# MCU.net
KiCad netlist of a schematic drawn in Altium Designer
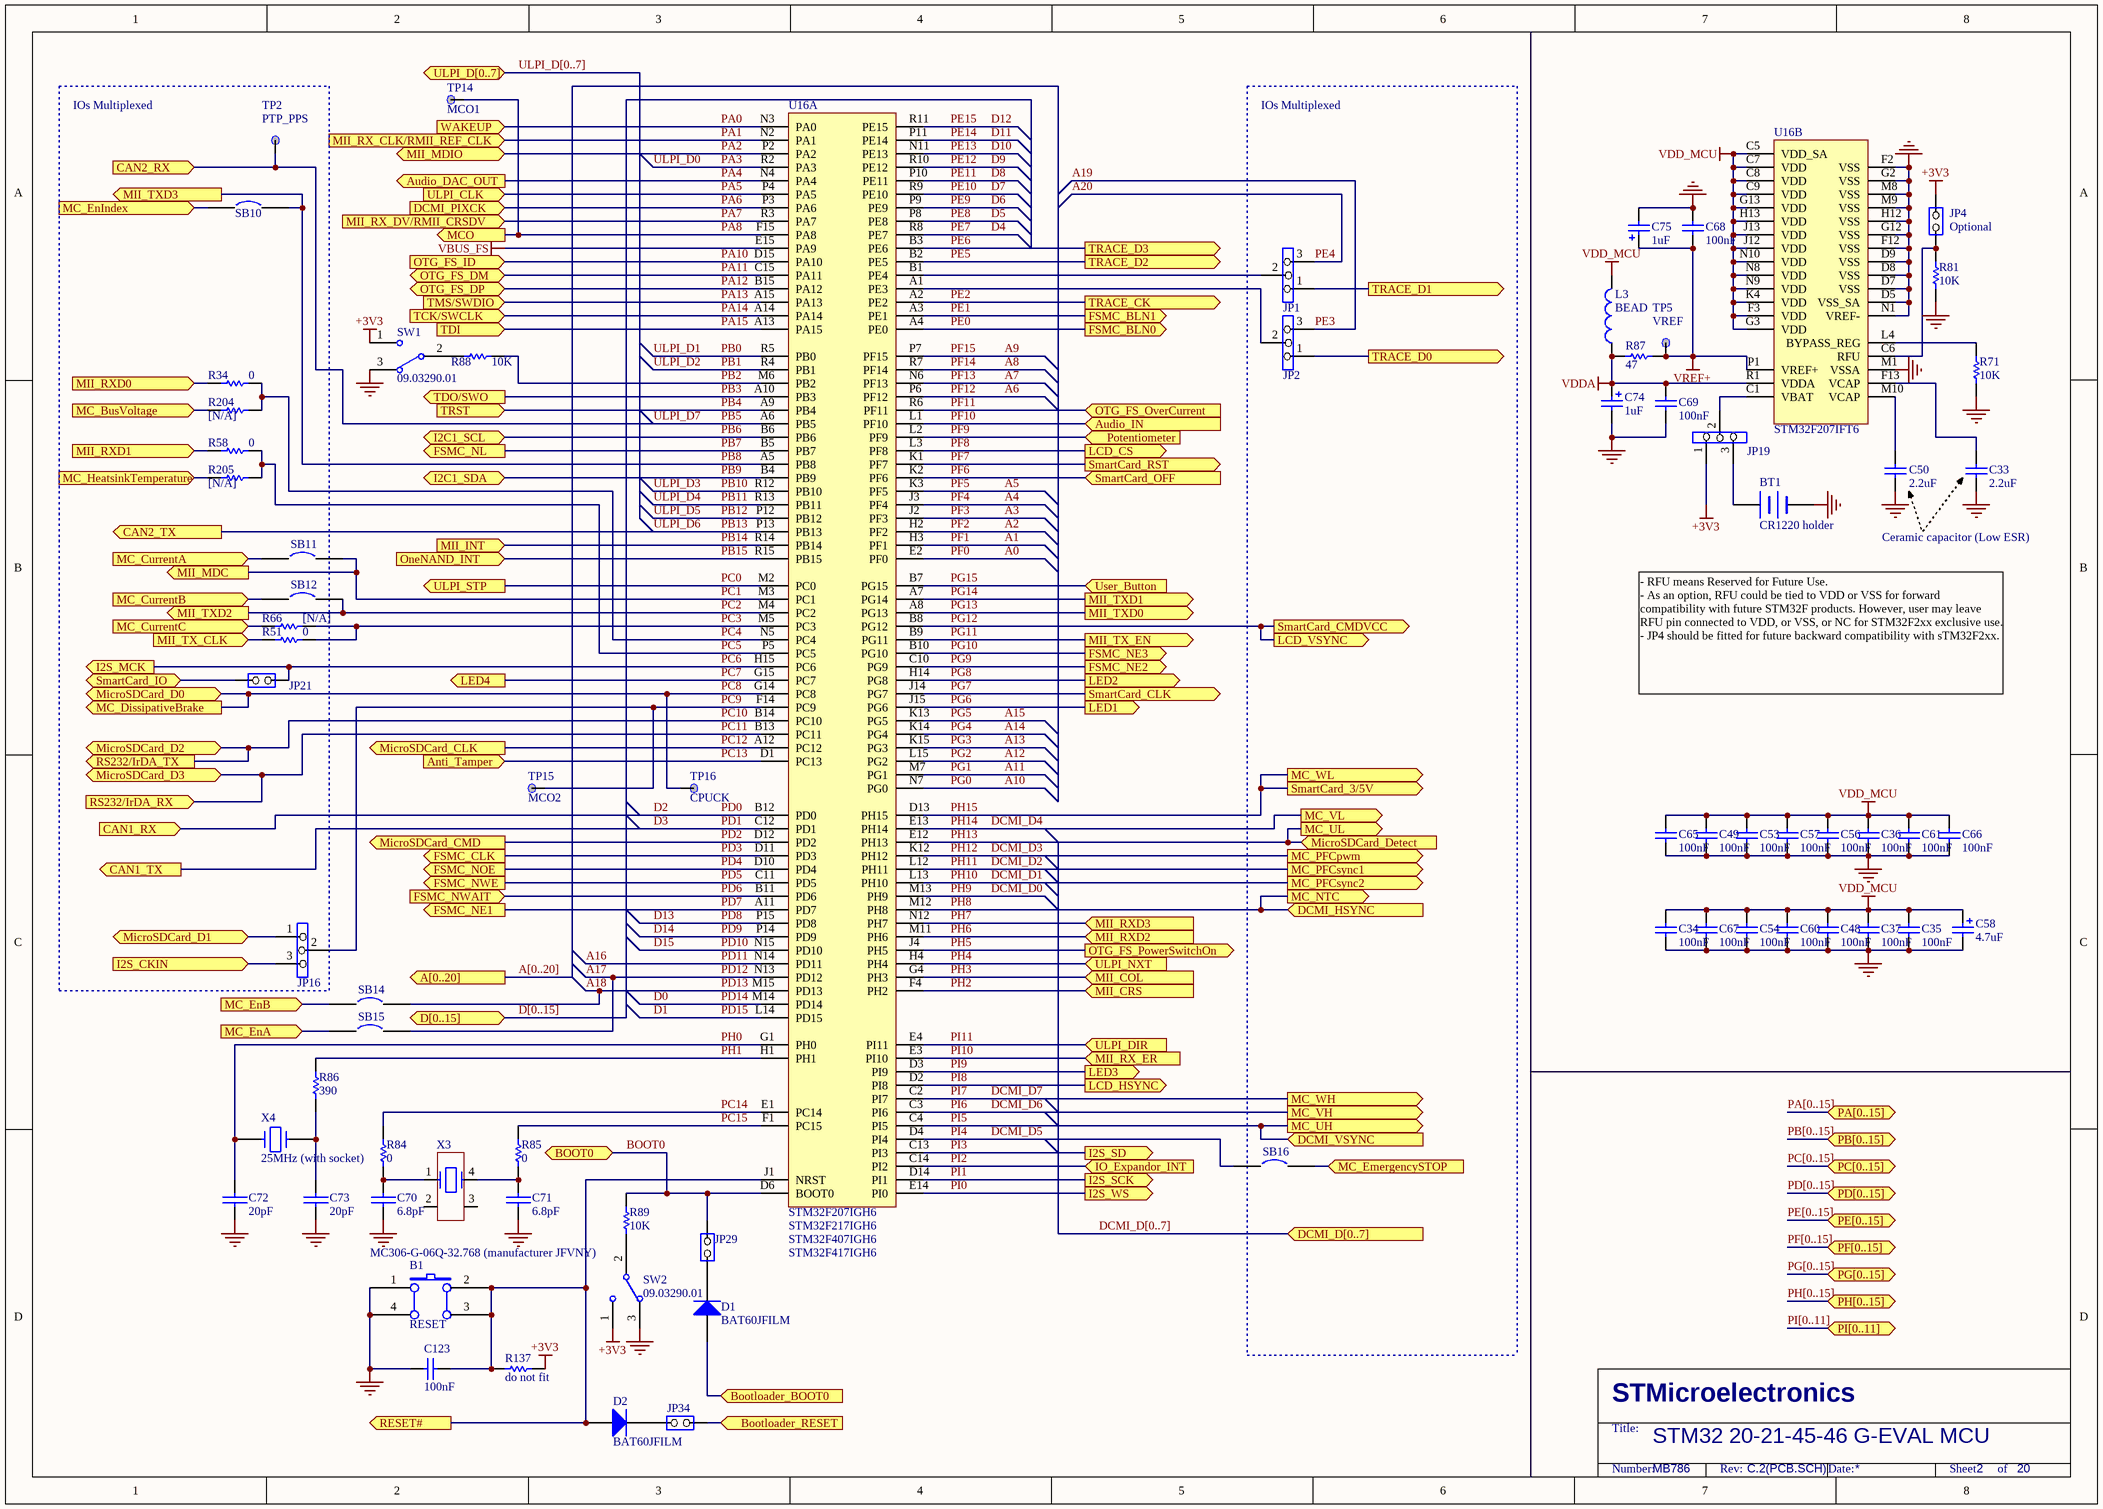
[diagram p0: MCU.SchDoc]

(export (version "E")
  (design (tool "Eeschema 10.0.6"))
  (components
    (comp (ref "B1")
      (value "RESET")
      (footprint "PB10")
      (description "SE PUSHBUTTON")
      (libsource (lib "Documents") (part "SW PUSHBUTTON"))
    )
    (comp (ref "BT1")
      (value "CR1220 holder")
      (footprint "LI1220_1")
      (description "Battery")
      (libsource (lib "*") (part "BATTERY"))
    )
    (comp (ref "C33")
      (value "2.2uF")
      (footprint "1206C")
      (description "Capacitor")
      (fields (field (name "PUBLISHER") "Altium Limited"))
      (libsource (lib "Miscellaneous Devices") (part "Cap"))
    )
    (comp (ref "C34")
      (value "100nF")
      (footprint "0402C")
      (description "Capacitor")
      (fields (field (name "PUBLISHER") "Altium Limited"))
      (libsource (lib "Miscellaneous Devices") (part "Cap"))
    )
    (comp (ref "C35")
      (value "100nF")
      (footprint "0402C")
      (description "Capacitor")
      (fields (field (name "PUBLISHER") "Altium Limited"))
      (libsource (lib "Miscellaneous Devices") (part "Cap"))
    )
    (comp (ref "C36")
      (value "100nF")
      (footprint "0402C")
      (description "Capacitor")
      (fields (field (name "PUBLISHER") "Altium Limited"))
      (libsource (lib "Miscellaneous Devices") (part "Cap"))
    )
    (comp (ref "C37")
      (value "100nF")
      (footprint "0402C")
      (description "Capacitor")
      (fields (field (name "PUBLISHER") "Altium Limited"))
      (libsource (lib "Miscellaneous Devices") (part "Cap"))
    )
    (comp (ref "C48")
      (value "100nF")
      (footprint "0402C")
      (description "Capacitor")
      (fields (field (name "PUBLISHER") "Altium Limited"))
      (libsource (lib "Miscellaneous Devices") (part "Cap"))
    )
    (comp (ref "C49")
      (value "100nF")
      (footprint "0402C")
      (description "Capacitor")
      (fields (field (name "PUBLISHER") "Altium Limited"))
      (libsource (lib "Miscellaneous Devices") (part "Cap"))
    )
    (comp (ref "C50")
      (value "2.2uF")
      (footprint "1206C")
      (description "Capacitor")
      (fields (field (name "PUBLISHER") "Altium Limited"))
      (libsource (lib "Miscellaneous Devices") (part "Cap"))
    )
    (comp (ref "C53")
      (value "100nF")
      (footprint "0402C")
      (description "Capacitor")
      (fields (field (name "PUBLISHER") "Altium Limited"))
      (libsource (lib "Miscellaneous Devices") (part "Cap"))
    )
    (comp (ref "C54")
      (value "100nF")
      (footprint "0402C")
      (description "Capacitor")
      (fields (field (name "PUBLISHER") "Altium Limited"))
      (libsource (lib "Miscellaneous Devices") (part "Cap"))
    )
    (comp (ref "C56")
      (value "100nF")
      (footprint "0402C")
      (description "Capacitor")
      (fields (field (name "PUBLISHER") "Altium Limited"))
      (libsource (lib "Miscellaneous Devices") (part "Cap"))
    )
    (comp (ref "C57")
      (value "100nF")
      (footprint "0402C")
      (description "Capacitor")
      (fields (field (name "PUBLISHER") "Altium Limited"))
      (libsource (lib "Miscellaneous Devices") (part "Cap"))
    )
    (comp (ref "C58")
      (value "4.7uF")
      (footprint "TAN-A")
      (description "Polarized Capacitor (Radial)")
      (fields (field (name "PUBLISHER") "Altium Limited"))
      (libsource (lib "Miscellaneous Devices") (part "Cap Pol1"))
    )
    (comp (ref "C60")
      (value "100nF")
      (footprint "0402C")
      (description "Capacitor")
      (fields (field (name "PUBLISHER") "Altium Limited"))
      (libsource (lib "Miscellaneous Devices") (part "Cap"))
    )
    (comp (ref "C61")
      (value "100nF")
      (footprint "0402C")
      (description "Capacitor")
      (fields (field (name "PUBLISHER") "Altium Limited"))
      (libsource (lib "Miscellaneous Devices") (part "Cap"))
    )
    (comp (ref "C65")
      (value "100nF")
      (footprint "0402C")
      (description "Capacitor")
      (fields (field (name "PUBLISHER") "Altium Limited"))
      (libsource (lib "Miscellaneous Devices") (part "Cap"))
    )
    (comp (ref "C66")
      (value "100nF")
      (footprint "0402C")
      (description "Capacitor")
      (fields (field (name "PUBLISHER") "Altium Limited"))
      (libsource (lib "Miscellaneous Devices") (part "Cap"))
    )
    (comp (ref "C67")
      (value "100nF")
      (footprint "0402C")
      (description "Capacitor")
      (fields (field (name "PUBLISHER") "Altium Limited"))
      (libsource (lib "Miscellaneous Devices") (part "Cap"))
    )
    (comp (ref "C68")
      (value "100nF")
      (footprint "0402C")
      (description "Capacitor")
      (fields (field (name "PUBLISHER") "Altium Limited"))
      (libsource (lib "Miscellaneous Devices") (part "Cap"))
    )
    (comp (ref "C69")
      (value "100nF")
      (footprint "0402C")
      (description "Capacitor")
      (fields (field (name "PUBLISHER") "Altium Limited"))
      (libsource (lib "Miscellaneous Devices") (part "Cap"))
    )
    (comp (ref "C70")
      (value "6.8pF")
      (footprint "0603C")
      (description "Capacitor")
      (libsource (lib "*") (part "CAP"))
    )
    (comp (ref "C71")
      (value "6.8pF")
      (footprint "0603C")
      (description "Capacitor")
      (libsource (lib "*") (part "CAP"))
    )
    (comp (ref "C72")
      (value "20pF")
      (footprint "0603C")
      (description "Capacitor")
      (libsource (lib "") (part "CAP_1"))
    )
    (comp (ref "C73")
      (value "20pF")
      (footprint "0603C")
      (description "Capacitor")
      (libsource (lib "") (part "CAP_1"))
    )
    (comp (ref "C74")
      (value "1uF")
      (footprint "TAN-A")
      (description "Polarized Capacitor (Radial)")
      (fields (field (name "PUBLISHER") "Altium Limited"))
      (libsource (lib "Miscellaneous Devices") (part "Cap Pol1"))
    )
    (comp (ref "C75")
      (value "1uF")
      (footprint "TAN-A")
      (description "Polarized Capacitor (Radial)")
      (fields (field (name "PUBLISHER") "Altium Limited"))
      (libsource (lib "Miscellaneous Devices") (part "Cap Pol1"))
    )
    (comp (ref "C123")
      (value "100nF")
      (footprint "0402C")
      (description "Capacitor")
      (fields (field (name "PUBLISHER") "Altium Limited"))
      (libsource (lib "Miscellaneous Devices") (part "CAP"))
    )
    (comp (ref "D1")
      (value "BAT60JFILM")
      (footprint "SOD-323")
      (description "Default Diode")
      (fields (field (name "PUBLISHER") "Altium Limited"))
      (libsource (lib "Miscellaneous Devices") (part "Diode"))
    )
    (comp (ref "D2")
      (value "BAT60JFILM")
      (footprint "SOD-323")
      (description "Default Diode")
      (fields (field (name "PUBLISHER") "Altium Limited"))
      (libsource (lib "Miscellaneous Devices") (part "Diode"))
    )
    (comp (ref "JP1") (value "~") (footprint "SIP3") (libsource (lib "STR910_SCHLIB") (part "Jumper3")))
    (comp (ref "JP2") (value "~") (footprint "SIP3") (libsource (lib "STR910_SCHLIB") (part "Jumper3")))
    (comp (ref "JP4") (value "~") (footprint "SIP2") (libsource (lib "*") (part "JP2")))
    (comp (ref "JP16") (value "~") (footprint "SIP3") (libsource (lib "STR910_SCHLIB") (part "Jumper3")))
    (comp (ref "JP19") (value "~") (footprint "SIP3") (libsource (lib "STR910_SCHLIB") (part "Jumper3")))
    (comp (ref "JP21") (value "~") (footprint "SIP2") (libsource (lib "*") (part "JP2")))
    (comp (ref "JP29") (value "~") (footprint "SIP2") (libsource (lib "*") (part "JP2")))
    (comp (ref "JP34") (value "~") (footprint "SIP2") (libsource (lib "*") (part "JP2")))
    (comp (ref "L3")
      (value "BEAD")
      (footprint "0603L")
      (description "Inductor")
      (fields (field (name "PUBLISHER") "Altium Limited"))
      (libsource (lib "Miscellaneous Devices") (part "Inductor"))
    )
    (comp (ref "R34")
      (value "0")
      (footprint "0603R")
      (description "Resistor")
      (fields (field (name "PUBLISHER") "Altium Limited"))
      (libsource (lib "Miscellaneous Devices") (part "res1"))
    )
    (comp (ref "R51")
      (value "0")
      (footprint "0603R")
      (description "Resistor")
      (fields (field (name "PUBLISHER") "Altium Limited"))
      (libsource (lib "Miscellaneous Devices") (part "res1"))
    )
    (comp (ref "R58")
      (value "0")
      (footprint "0603R")
      (description "Resistor")
      (fields (field (name "PUBLISHER") "Altium Limited"))
      (libsource (lib "Miscellaneous Devices") (part "res1"))
    )
    (comp (ref "R66")
      (value "[N/A]")
      (footprint "0603R")
      (description "Resistor")
      (fields (field (name "PUBLISHER") "Altium Limited"))
      (libsource (lib "Miscellaneous Devices") (part "res1"))
    )
    (comp (ref "R71")
      (value "10K")
      (footprint "0402R")
      (description "Resistor")
      (fields (field (name "PUBLISHER") "Altium Limited"))
      (libsource (lib "Miscellaneous Devices") (part "Res1"))
    )
    (comp (ref "R81")
      (value "10K")
      (footprint "0402R")
      (description "Resistor")
      (fields (field (name "PUBLISHER") "Altium Limited"))
      (libsource (lib "Miscellaneous Devices") (part "Res1"))
    )
    (comp (ref "R84")
      (value "0")
      (footprint "0603R")
      (description "Resistor")
      (fields (field (name "PUBLISHER") "Altium Limited"))
      (libsource (lib "Miscellaneous Devices") (part "Res1"))
    )
    (comp (ref "R85")
      (value "0")
      (footprint "0603R")
      (description "Resistor")
      (fields (field (name "PUBLISHER") "Altium Limited"))
      (libsource (lib "Miscellaneous Devices") (part "Res1"))
    )
    (comp (ref "R86")
      (value "390")
      (footprint "0603R")
      (description "Resistor")
      (fields (field (name "PUBLISHER") "Altium Limited"))
      (libsource (lib "Miscellaneous Devices") (part "Res1"))
    )
    (comp (ref "R87")
      (value "47")
      (footprint "0603R")
      (description "Resistor")
      (fields (field (name "PUBLISHER") "Altium Limited"))
      (libsource (lib "Miscellaneous Devices") (part "Res1"))
    )
    (comp (ref "R88")
      (value "10K")
      (footprint "0402R")
      (description "Resistor")
      (fields (field (name "PUBLISHER") "Altium Limited"))
      (libsource (lib "Miscellaneous Devices") (part "res1"))
    )
    (comp (ref "R89")
      (value "10K")
      (footprint "0402R")
      (description "Resistor")
      (fields (field (name "PUBLISHER") "Altium Limited"))
      (libsource (lib "Miscellaneous Devices") (part "res1"))
    )
    (comp (ref "R137")
      (value "do not fit")
      (footprint "0603R")
      (description "Resistor")
      (fields (field (name "PUBLISHER") "Altium Limited"))
      (libsource (lib "Miscellaneous Devices") (part "res1"))
    )
    (comp (ref "R204")
      (value "[N/A]")
      (footprint "0603R")
      (description "Resistor")
      (fields (field (name "PUBLISHER") "Altium Limited"))
      (libsource (lib "Miscellaneous Devices") (part "res1"))
    )
    (comp (ref "R205")
      (value "[N/A]")
      (footprint "0603R")
      (description "Resistor")
      (fields (field (name "PUBLISHER") "Altium Limited"))
      (libsource (lib "Miscellaneous Devices") (part "res1"))
    )
    (comp (ref "SB10")
      (value "~")
      (footprint "JP2_SMD")
      (description "Circuit Breaker")
      (fields (field (name "PUBLISHER") "Altium Limited"))
      (libsource (lib "Miscellaneous Devices") (part "Circuit Breaker"))
    )
    (comp (ref "SB11")
      (value "~")
      (footprint "JP2_SMD")
      (description "Circuit Breaker")
      (fields (field (name "PUBLISHER") "Altium Limited"))
      (libsource (lib "Miscellaneous Devices") (part "Circuit Breaker"))
    )
    (comp (ref "SB12")
      (value "~")
      (footprint "JP2_SMD")
      (description "Circuit Breaker")
      (fields (field (name "PUBLISHER") "Altium Limited"))
      (libsource (lib "Miscellaneous Devices") (part "Circuit Breaker"))
    )
    (comp (ref "SB14")
      (value "~")
      (footprint "JP2_SMD")
      (description "Circuit Breaker")
      (fields (field (name "PUBLISHER") "Altium Limited"))
      (libsource (lib "Miscellaneous Devices") (part "Circuit Breaker"))
    )
    (comp (ref "SB15")
      (value "~")
      (footprint "JP2_SMD")
      (description "Circuit Breaker")
      (fields (field (name "PUBLISHER") "Altium Limited"))
      (libsource (lib "Miscellaneous Devices") (part "Circuit Breaker"))
    )
    (comp (ref "SB16")
      (value "~")
      (footprint "JP2_SMD")
      (description "Circuit Breaker")
      (fields (field (name "PUBLISHER") "Altium Limited"))
      (libsource (lib "Miscellaneous Devices") (part "Circuit Breaker"))
    )
    (comp (ref "SW1")
      (value "09.03290.01")
      (footprint "SIP3")
      (description "SPDT Subminiature Toggle Switch, Right Angle Mounting, Vertical Actuation")
      (fields (field (name "PUBLISHER") "Altium Limited"))
      (libsource (lib "Miscellaneous Devices") (part "SW-SPDT"))
    )
    (comp (ref "SW2")
      (value "09.03290.01")
      (footprint "SIP3")
      (description "SPDT Subminiature Toggle Switch, Right Angle Mounting, Vertical Actuation")
      (fields (field (name "PUBLISHER") "Altium Limited"))
      (libsource (lib "Miscellaneous Devices") (part "SW-SPDT"))
    )
    (comp (ref "TP2") (value "PTP_PPS") (footprint "TP") (libsource (lib "*") (part "TP")))
    (comp (ref "TP5") (value "VREF") (footprint "TP") (libsource (lib "*") (part "TP")))
    (comp (ref "TP14") (value "MCO1") (footprint "TP") (libsource (lib "*") (part "TP")))
    (comp (ref "TP15") (value "MCO2") (footprint "TP") (libsource (lib "*") (part "TP")))
    (comp (ref "TP16") (value "CPUCK") (footprint "TP") (libsource (lib "*") (part "TP")))
    (comp (ref "U16")
      (value "STM32F207IGH6")
      (footprint "UFBGA176")
      (libsource (lib "") (part "MANGUSTA_BGA176_1"))
    )
    (comp (ref "X3")
      (value "MC306-G-06Q-32.768 (manufacturer JFVNY)")
      (footprint "SM8")
      (libsource (lib "*") (part "MC306"))
    )
    (comp (ref "X4")
      (value "25MHz (with socket)")
      (footprint "XTAL_socket")
      (description "Crystal")
      (libsource (lib "*") (part "CRYSTAL"))
    )
  )
  (nets
    (net (code "2") (name "+3V3") (class "Default")
      (node (ref "JP19") (pin "1") (pintype "passive"))
      (node (ref "JP4") (pin "1") (pinfunction "COMMON_1") (pintype "passive"))
      (node (ref "R137") (pin "2") (pinfunction "2_2") (pintype "passive"))
      (node (ref "SW1") (pin "1") (pintype "passive"))
      (node (ref "SW2") (pin "1") (pintype "passive"))
    )
    (net (code "3") (name "/A0") (class "Default")
      (node (ref "U16") (pin "E2") (pinfunction "PF0_E2") (pintype "passive"))
    )
    (net (code "4") (name "/A1") (class "Default")
      (node (ref "U16") (pin "H3") (pinfunction "PF1_H3") (pintype "passive"))
    )
    (net (code "5") (name "/A2") (class "Default")
      (node (ref "U16") (pin "H2") (pinfunction "PF2_H2") (pintype "passive"))
    )
    (net (code "6") (name "/A3") (class "Default")
      (node (ref "U16") (pin "J2") (pinfunction "PF3_J2") (pintype "passive"))
    )
    (net (code "7") (name "/A4") (class "Default")
      (node (ref "U16") (pin "J3") (pinfunction "PF4_J3") (pintype "passive"))
    )
    (net (code "8") (name "/A5") (class "Default")
      (node (ref "U16") (pin "K3") (pinfunction "PF5_K3") (pintype "passive"))
    )
    (net (code "9") (name "/A6") (class "Default")
      (node (ref "U16") (pin "P6") (pinfunction "PF12_P6") (pintype "passive"))
    )
    (net (code "10") (name "/A7") (class "Default")
      (node (ref "U16") (pin "N6") (pinfunction "PF13_N6") (pintype "passive"))
    )
    (net (code "11") (name "/A8") (class "Default")
      (node (ref "U16") (pin "R7") (pinfunction "PF14_R7") (pintype "passive"))
    )
    (net (code "12") (name "/A9") (class "Default")
      (node (ref "U16") (pin "P7") (pinfunction "PF15_P7") (pintype "passive"))
    )
    (net (code "13") (name "/A10") (class "Default")
      (node (ref "U16") (pin "N7") (pinfunction "PG0_N7") (pintype "passive"))
    )
    (net (code "14") (name "/A11") (class "Default")
      (node (ref "U16") (pin "M7") (pinfunction "PG1_M7") (pintype "passive"))
    )
    (net (code "15") (name "/A12") (class "Default")
      (node (ref "U16") (pin "L15") (pinfunction "PG2_L15") (pintype "passive"))
    )
    (net (code "16") (name "/A13") (class "Default")
      (node (ref "U16") (pin "K15") (pinfunction "PG3_K15") (pintype "passive"))
    )
    (net (code "17") (name "/A14") (class "Default")
      (node (ref "U16") (pin "K14") (pinfunction "PG4_K14") (pintype "passive"))
    )
    (net (code "18") (name "/A15") (class "Default")
      (node (ref "U16") (pin "K13") (pinfunction "PG5_K13") (pintype "passive"))
    )
    (net (code "19") (name "/A16") (class "Default")
      (node (ref "U16") (pin "N14") (pinfunction "PD11_N14") (pintype "passive"))
    )
    (net (code "20") (name "/A17") (class "Default")
      (node (ref "SB15") (pin "2") (pinfunction "2_2") (pintype "passive"))
      (node (ref "U16") (pin "N13") (pinfunction "PD12_N13") (pintype "passive"))
    )
    (net (code "21") (name "/A18") (class "Default")
      (node (ref "SB14") (pin "2") (pinfunction "2_2") (pintype "passive"))
      (node (ref "U16") (pin "M15") (pinfunction "PD13_M15") (pintype "passive"))
    )
    (net (code "22") (name "/A19") (class "Default") (node (ref "JP2") (pin "3") (pintype "passive")))
    (net (code "23") (name "/A20") (class "Default") (node (ref "JP1") (pin "3") (pintype "passive")))
    (net (code "25") (name "/BOOT0") (class "Default")
      (node (ref "JP29") (pin "1") (pinfunction "COMMON_1") (pintype "passive"))
      (node (ref "R89") (pin "1") (pinfunction "1_1") (pintype "passive"))
      (node (ref "U16") (pin "D6") (pinfunction "BOOT0_D6") (pintype "passive"))
    )
    (net (code "26") (name "/Bootloader_BOOT0") (class "Default")
      (node (ref "D1") (pin "1") (pinfunction "A_1") (pintype "passive"))
    )
    (net (code "27") (name "/Bootloader_RESET") (class "Default")
      (node (ref "JP34") (pin "2") (pinfunction "NO_2") (pintype "passive"))
    )
    (net (code "28") (name "/D0") (class "Default")
      (node (ref "U16") (pin "M14") (pinfunction "PD14_M14") (pintype "passive"))
    )
    (net (code "29") (name "/D1") (class "Default")
      (node (ref "U16") (pin "L14") (pinfunction "PD15_L14") (pintype "passive"))
    )
    (net (code "30") (name "/D2") (class "Default")
      (node (ref "U16") (pin "B12") (pinfunction "PD0_B12") (pintype "passive"))
    )
    (net (code "31") (name "/D3") (class "Default")
      (node (ref "U16") (pin "C12") (pinfunction "PD1_C12") (pintype "passive"))
    )
    (net (code "32") (name "/D4") (class "Default")
      (node (ref "U16") (pin "R8") (pinfunction "PE7_R8") (pintype "passive"))
    )
    (net (code "33") (name "/D5") (class "Default")
      (node (ref "U16") (pin "P8") (pinfunction "PE8_P8") (pintype "passive"))
    )
    (net (code "34") (name "/D6") (class "Default")
      (node (ref "U16") (pin "P9") (pinfunction "PE9_P9") (pintype "passive"))
    )
    (net (code "35") (name "/D7") (class "Default")
      (node (ref "U16") (pin "R9") (pinfunction "PE10_R9") (pintype "passive"))
    )
    (net (code "36") (name "/D8") (class "Default")
      (node (ref "U16") (pin "P10") (pinfunction "PE11_P10") (pintype "passive"))
    )
    (net (code "37") (name "/D9") (class "Default")
      (node (ref "U16") (pin "R10") (pinfunction "PE12_R10") (pintype "passive"))
    )
    (net (code "38") (name "/D10") (class "Default")
      (node (ref "U16") (pin "N11") (pinfunction "PE13_N11") (pintype "passive"))
    )
    (net (code "39") (name "/D11") (class "Default")
      (node (ref "U16") (pin "P11") (pinfunction "PE14_P11") (pintype "passive"))
    )
    (net (code "40") (name "/D12") (class "Default")
      (node (ref "U16") (pin "R11") (pinfunction "PE15_R11") (pintype "passive"))
    )
    (net (code "41") (name "/D13") (class "Default")
      (node (ref "U16") (pin "P15") (pinfunction "PD8_P15") (pintype "passive"))
    )
    (net (code "42") (name "/D14") (class "Default")
      (node (ref "U16") (pin "P14") (pinfunction "PD9_P14") (pintype "passive"))
    )
    (net (code "43") (name "/D15") (class "Default")
      (node (ref "U16") (pin "N15") (pinfunction "PD10_N15") (pintype "passive"))
    )
    (net (code "46") (name "/I2S_CKIN") (class "Default") (node (ref "JP16") (pin "3") (pintype "passive")))
    (net (code "47") (name "/MC_BusVoltage") (class "Default")
      (node (ref "R204") (pin "1") (pinfunction "1_1") (pintype "passive"))
    )
    (net (code "48") (name "/MC_CurrentA") (class "Default")
      (node (ref "SB11") (pin "1") (pinfunction "1_1") (pintype "passive"))
    )
    (net (code "49") (name "/MC_CurrentB") (class "Default")
      (node (ref "SB12") (pin "1") (pinfunction "1_1") (pintype "passive"))
    )
    (net (code "50") (name "/MC_CurrentC") (class "Default")
      (node (ref "R66") (pin "1") (pinfunction "1_1") (pintype "passive"))
    )
    (net (code "51") (name "/MC_EmergencySTOP") (class "Default")
      (node (ref "SB16") (pin "2") (pinfunction "2_2") (pintype "passive"))
    )
    (net (code "52") (name "/MC_EnA") (class "Default")
      (node (ref "SB15") (pin "1") (pinfunction "1_1") (pintype "passive"))
    )
    (net (code "53") (name "/MC_EnB") (class "Default")
      (node (ref "SB14") (pin "1") (pinfunction "1_1") (pintype "passive"))
    )
    (net (code "54") (name "/MC_EnIndex") (class "Default")
      (node (ref "SB10") (pin "1") (pinfunction "1_1") (pintype "passive"))
    )
    (net (code "55") (name "/MC_HeatsinkTemperature") (class "Default")
      (node (ref "R205") (pin "1") (pinfunction "1_1") (pintype "passive"))
    )
    (net (code "56") (name "/MII_RXD0") (class "Default")
      (node (ref "R34") (pin "1") (pinfunction "1_1") (pintype "passive"))
    )
    (net (code "57") (name "/MII_RXD1") (class "Default")
      (node (ref "R58") (pin "1") (pinfunction "1_1") (pintype "passive"))
    )
    (net (code "58") (name "/MII_TX_CLK") (class "Default")
      (node (ref "R51") (pin "1") (pinfunction "1_1") (pintype "passive"))
    )
    (net (code "59") (name "/MicroSDCard_D1") (class "Default")
      (node (ref "JP16") (pin "1") (pintype "passive"))
    )
    (net (code "60") (name "/PA0") (class "Default")
      (node (ref "U16") (pin "N3") (pinfunction "PA0_N3") (pintype "passive"))
    )
    (net (code "61") (name "/PA1") (class "Default")
      (node (ref "U16") (pin "N2") (pinfunction "PA1_N2") (pintype "passive"))
    )
    (net (code "62") (name "/PA2") (class "Default")
      (node (ref "U16") (pin "P2") (pinfunction "PA2_P2") (pintype "passive"))
    )
    (net (code "63") (name "/PA4") (class "Default")
      (node (ref "U16") (pin "N4") (pinfunction "PA4_N4") (pintype "passive"))
    )
    (net (code "64") (name "/PA5") (class "Default")
      (node (ref "U16") (pin "P4") (pinfunction "PA5_P4") (pintype "passive"))
    )
    (net (code "65") (name "/PA6") (class "Default")
      (node (ref "U16") (pin "P3") (pinfunction "PA6_P3") (pintype "passive"))
    )
    (net (code "66") (name "/PA7") (class "Default")
      (node (ref "U16") (pin "R3") (pinfunction "PA7_R3") (pintype "passive"))
    )
    (net (code "67") (name "/PA8") (class "Default")
      (node (ref "TP14") (pin "1") (pinfunction "1_1") (pintype "passive"))
      (node (ref "U16") (pin "F15") (pinfunction "PA8_F15") (pintype "passive"))
    )
    (net (code "68") (name "/PA10") (class "Default")
      (node (ref "U16") (pin "D15") (pinfunction "PA10_D15") (pintype "passive"))
    )
    (net (code "69") (name "/PA11") (class "Default")
      (node (ref "U16") (pin "C15") (pinfunction "PA11_C15") (pintype "passive"))
    )
    (net (code "70") (name "/PA12") (class "Default")
      (node (ref "U16") (pin "B15") (pinfunction "PA12_B15") (pintype "passive"))
    )
    (net (code "71") (name "/PA13") (class "Default")
      (node (ref "U16") (pin "A15") (pinfunction "PA13_A15") (pintype "passive"))
    )
    (net (code "72") (name "/PA14") (class "Default")
      (node (ref "U16") (pin "A14") (pinfunction "PA14_A14") (pintype "passive"))
    )
    (net (code "73") (name "/PA15") (class "Default")
      (node (ref "U16") (pin "A13") (pinfunction "PA15_A13") (pintype "passive"))
    )
    (net (code "75") (name "/PB2") (class "Default")
      (node (ref "R88") (pin "1") (pinfunction "1_1") (pintype "passive"))
      (node (ref "U16") (pin "M6") (pinfunction "PB2_M6") (pintype "passive"))
    )
    (net (code "76") (name "/PB3") (class "Default")
      (node (ref "U16") (pin "A10") (pinfunction "PB3_A10") (pintype "passive"))
    )
    (net (code "77") (name "/PB4") (class "Default")
      (node (ref "U16") (pin "A9") (pinfunction "PB4_A9") (pintype "passive"))
    )
    (net (code "78") (name "/PB6") (class "Default")
      (node (ref "U16") (pin "B6") (pinfunction "PB6_B6") (pintype "passive"))
    )
    (net (code "79") (name "/PB7") (class "Default")
      (node (ref "U16") (pin "B5") (pinfunction "PB7_B5") (pintype "passive"))
    )
    (net (code "80") (name "/PB8") (class "Default")
      (node (ref "SB10") (pin "2") (pinfunction "2_2") (pintype "passive"))
      (node (ref "U16") (pin "A5") (pinfunction "PB8_A5") (pintype "passive"))
    )
    (net (code "81") (name "/PB9") (class "Default")
      (node (ref "U16") (pin "B4") (pinfunction "PB9_B4") (pintype "passive"))
    )
    (net (code "82") (name "/PB14") (class "Default")
      (node (ref "U16") (pin "R14") (pinfunction "PB14_R14") (pintype "passive"))
    )
    (net (code "83") (name "/PB15") (class "Default")
      (node (ref "U16") (pin "R15") (pinfunction "PB15_R15") (pintype "passive"))
    )
    (net (code "85") (name "/PC0") (class "Default")
      (node (ref "U16") (pin "M2") (pinfunction "PC0_M2") (pintype "passive"))
    )
    (net (code "86") (name "/PC1") (class "Default")
      (node (ref "SB11") (pin "2") (pinfunction "2_2") (pintype "passive"))
      (node (ref "U16") (pin "M3") (pinfunction "PC1_M3") (pintype "passive"))
    )
    (net (code "87") (name "/PC2") (class "Default")
      (node (ref "SB12") (pin "2") (pinfunction "2_2") (pintype "passive"))
      (node (ref "U16") (pin "M4") (pinfunction "PC2_M4") (pintype "passive"))
    )
    (net (code "88") (name "/PC3") (class "Default")
      (node (ref "R51") (pin "2") (pinfunction "2_2") (pintype "passive"))
      (node (ref "R66") (pin "2") (pinfunction "2_2") (pintype "passive"))
      (node (ref "U16") (pin "M5") (pinfunction "PC3_M5") (pintype "passive"))
    )
    (net (code "89") (name "/PC4") (class "Default")
      (node (ref "R204") (pin "2") (pinfunction "2_2") (pintype "passive"))
      (node (ref "R34") (pin "2") (pinfunction "2_2") (pintype "passive"))
      (node (ref "U16") (pin "N5") (pinfunction "PC4_N5") (pintype "passive"))
    )
    (net (code "90") (name "/PC5") (class "Default")
      (node (ref "R205") (pin "2") (pinfunction "2_2") (pintype "passive"))
      (node (ref "R58") (pin "2") (pinfunction "2_2") (pintype "passive"))
      (node (ref "U16") (pin "P5") (pinfunction "PC5_P5") (pintype "passive"))
    )
    (net (code "91") (name "/PC6") (class "Default")
      (node (ref "JP21") (pin "1") (pinfunction "COMMON_1") (pintype "passive"))
      (node (ref "U16") (pin "H15") (pinfunction "PC6_H15") (pintype "passive"))
    )
    (net (code "92") (name "/PC7") (class "Default")
      (node (ref "U16") (pin "G15") (pinfunction "PC7_G15") (pintype "passive"))
    )
    (net (code "93") (name "/PC8") (class "Default")
      (node (ref "TP16") (pin "1") (pinfunction "1_1") (pintype "passive"))
      (node (ref "U16") (pin "G14") (pinfunction "PC8_G14") (pintype "passive"))
    )
    (net (code "94") (name "/PC9") (class "Default")
      (node (ref "JP16") (pin "2") (pintype "passive"))
      (node (ref "TP15") (pin "1") (pinfunction "1_1") (pintype "passive"))
      (node (ref "U16") (pin "F14") (pinfunction "PC9_F14") (pintype "passive"))
    )
    (net (code "95") (name "/PC10") (class "Default")
      (node (ref "U16") (pin "B14") (pinfunction "PC10_B14") (pintype "passive"))
    )
    (net (code "96") (name "/PC11") (class "Default")
      (node (ref "U16") (pin "B13") (pinfunction "PC11_B13") (pintype "passive"))
    )
    (net (code "97") (name "/PC12") (class "Default")
      (node (ref "U16") (pin "A12") (pinfunction "PC12_A12") (pintype "passive"))
    )
    (net (code "98") (name "/PC13") (class "Default")
      (node (ref "U16") (pin "D1") (pinfunction "PC13_D1") (pintype "passive"))
    )
    (net (code "99") (name "/PC14") (class "Default")
      (node (ref "R84") (pin "2") (pinfunction "2_2") (pintype "passive"))
      (node (ref "U16") (pin "E1") (pinfunction "PC14_E1") (pintype "passive"))
    )
    (net (code "100") (name "/PC15") (class "Default")
      (node (ref "R85") (pin "2") (pinfunction "2_2") (pintype "passive"))
      (node (ref "U16") (pin "F1") (pinfunction "PC15_F1") (pintype "passive"))
    )
    (net (code "102") (name "/PD2") (class "Default")
      (node (ref "U16") (pin "D12") (pinfunction "PD2_D12") (pintype "passive"))
    )
    (net (code "103") (name "/PD3") (class "Default")
      (node (ref "U16") (pin "D11") (pinfunction "PD3_D11") (pintype "passive"))
    )
    (net (code "104") (name "/PD4") (class "Default")
      (node (ref "U16") (pin "D10") (pinfunction "PD4_D10") (pintype "passive"))
    )
    (net (code "105") (name "/PD5") (class "Default")
      (node (ref "U16") (pin "C11") (pinfunction "PD5_C11") (pintype "passive"))
    )
    (net (code "106") (name "/PD6") (class "Default")
      (node (ref "U16") (pin "B11") (pinfunction "PD6_B11") (pintype "passive"))
    )
    (net (code "107") (name "/PD7") (class "Default")
      (node (ref "U16") (pin "A11") (pinfunction "PD7_A11") (pintype "passive"))
    )
    (net (code "109") (name "/PE0") (class "Default")
      (node (ref "U16") (pin "A4") (pinfunction "PE0_A4") (pintype "passive"))
    )
    (net (code "110") (name "/PE1") (class "Default")
      (node (ref "U16") (pin "A3") (pinfunction "PE1_A3") (pintype "passive"))
    )
    (net (code "111") (name "/PE2") (class "Default")
      (node (ref "U16") (pin "A2") (pinfunction "PE2_A2") (pintype "passive"))
    )
    (net (code "112") (name "/PE5") (class "Default")
      (node (ref "U16") (pin "B2") (pinfunction "PE5_B2") (pintype "passive"))
    )
    (net (code "113") (name "/PE6") (class "Default")
      (node (ref "U16") (pin "B3") (pinfunction "PE6_B3") (pintype "passive"))
    )
    (net (code "115") (name "/PF6") (class "Default")
      (node (ref "U16") (pin "K2") (pinfunction "PF6_K2") (pintype "passive"))
    )
    (net (code "116") (name "/PF7") (class "Default")
      (node (ref "U16") (pin "K1") (pinfunction "PF7_K1") (pintype "passive"))
    )
    (net (code "117") (name "/PF8") (class "Default")
      (node (ref "U16") (pin "L3") (pinfunction "PF8_L3") (pintype "passive"))
    )
    (net (code "118") (name "/PF9") (class "Default")
      (node (ref "U16") (pin "L2") (pinfunction "PF9_L2") (pintype "passive"))
    )
    (net (code "119") (name "/PF10") (class "Default")
      (node (ref "U16") (pin "L1") (pinfunction "PF10_L1") (pintype "passive"))
    )
    (net (code "120") (name "/PF11") (class "Default")
      (node (ref "U16") (pin "R6") (pinfunction "PF11_R6") (pintype "passive"))
    )
    (net (code "122") (name "/PG6") (class "Default")
      (node (ref "U16") (pin "J15") (pinfunction "PG6_J15") (pintype "passive"))
    )
    (net (code "123") (name "/PG7") (class "Default")
      (node (ref "U16") (pin "J14") (pinfunction "PG7_J14") (pintype "passive"))
    )
    (net (code "124") (name "/PG8") (class "Default")
      (node (ref "U16") (pin "H14") (pinfunction "PG8_H14") (pintype "passive"))
    )
    (net (code "125") (name "/PG9") (class "Default")
      (node (ref "U16") (pin "C10") (pinfunction "PG9_C10") (pintype "passive"))
    )
    (net (code "126") (name "/PG10") (class "Default")
      (node (ref "U16") (pin "B10") (pinfunction "PG10_B10") (pintype "passive"))
    )
    (net (code "127") (name "/PG11") (class "Default")
      (node (ref "U16") (pin "B9") (pinfunction "PG11_B9") (pintype "passive"))
    )
    (net (code "128") (name "/PG12") (class "Default")
      (node (ref "U16") (pin "B8") (pinfunction "PG12_B8") (pintype "passive"))
    )
    (net (code "129") (name "/PG13") (class "Default")
      (node (ref "U16") (pin "A8") (pinfunction "PG13_A8") (pintype "passive"))
    )
    (net (code "130") (name "/PG14") (class "Default")
      (node (ref "U16") (pin "A7") (pinfunction "PG14_A7") (pintype "passive"))
    )
    (net (code "131") (name "/PG15") (class "Default")
      (node (ref "U16") (pin "B7") (pinfunction "PG15_B7") (pintype "passive"))
    )
    (net (code "133") (name "/PH0") (class "Default")
      (node (ref "C72") (pin "1") (pinfunction "1_1") (pintype "passive"))
      (node (ref "U16") (pin "G1") (pinfunction "PH0_G1") (pintype "passive"))
      (node (ref "X4") (pin "2") (pinfunction "2_2") (pintype "passive"))
    )
    (net (code "134") (name "/PH1") (class "Default")
      (node (ref "R86") (pin "1") (pinfunction "1_1") (pintype "passive"))
      (node (ref "U16") (pin "H1") (pinfunction "PH1_H1") (pintype "passive"))
    )
    (net (code "135") (name "/PH2") (class "Default")
      (node (ref "U16") (pin "F4") (pinfunction "PH2_F4") (pintype "passive"))
    )
    (net (code "136") (name "/PH3") (class "Default")
      (node (ref "U16") (pin "G4") (pinfunction "PH3_G4") (pintype "passive"))
    )
    (net (code "137") (name "/PH4") (class "Default")
      (node (ref "U16") (pin "H4") (pinfunction "PH4_H4") (pintype "passive"))
    )
    (net (code "138") (name "/PH5") (class "Default")
      (node (ref "U16") (pin "J4") (pinfunction "PH5_J4") (pintype "passive"))
    )
    (net (code "139") (name "/PH6") (class "Default")
      (node (ref "U16") (pin "M11") (pinfunction "PH6_M11") (pintype "passive"))
    )
    (net (code "140") (name "/PH7") (class "Default")
      (node (ref "U16") (pin "N12") (pinfunction "PH7_N12") (pintype "passive"))
    )
    (net (code "141") (name "/PH8") (class "Default")
      (node (ref "U16") (pin "M12") (pinfunction "PH8_M12") (pintype "passive"))
    )
    (net (code "142") (name "/PH9") (class "Default")
      (node (ref "U16") (pin "M13") (pinfunction "PH9_M13") (pintype "passive"))
    )
    (net (code "143") (name "/PH10") (class "Default")
      (node (ref "U16") (pin "L13") (pinfunction "PH10_L13") (pintype "passive"))
    )
    (net (code "144") (name "/PH11") (class "Default")
      (node (ref "U16") (pin "L12") (pinfunction "PH11_L12") (pintype "passive"))
    )
    (net (code "145") (name "/PH12") (class "Default")
      (node (ref "U16") (pin "K12") (pinfunction "PH12_K12") (pintype "passive"))
    )
    (net (code "146") (name "/PH13") (class "Default")
      (node (ref "U16") (pin "E12") (pinfunction "PH13_E12") (pintype "passive"))
    )
    (net (code "147") (name "/PH14") (class "Default")
      (node (ref "U16") (pin "E13") (pinfunction "PH14_E13") (pintype "passive"))
    )
    (net (code "148") (name "/PH15") (class "Default")
      (node (ref "U16") (pin "D13") (pinfunction "PH15_D13") (pintype "passive"))
    )
    (net (code "150") (name "/PI0") (class "Default")
      (node (ref "U16") (pin "E14") (pinfunction "PI0_E14") (pintype "passive"))
    )
    (net (code "151") (name "/PI1") (class "Default")
      (node (ref "U16") (pin "D14") (pinfunction "PI1_D14") (pintype "passive"))
    )
    (net (code "152") (name "/PI2") (class "Default")
      (node (ref "U16") (pin "C14") (pinfunction "PI2_C14") (pintype "passive"))
    )
    (net (code "153") (name "/PI3") (class "Default")
      (node (ref "U16") (pin "C13") (pinfunction "PI3_C13") (pintype "passive"))
    )
    (net (code "154") (name "/PI4") (class "Default")
      (node (ref "SB16") (pin "1") (pinfunction "1_1") (pintype "passive"))
      (node (ref "U16") (pin "D4") (pinfunction "PI4_D4") (pintype "passive"))
    )
    (net (code "155") (name "/PI5") (class "Default")
      (node (ref "U16") (pin "C4") (pinfunction "PI5_C4") (pintype "passive"))
    )
    (net (code "156") (name "/PI6") (class "Default")
      (node (ref "U16") (pin "C3") (pinfunction "PI6_C3") (pintype "passive"))
    )
    (net (code "157") (name "/PI7") (class "Default")
      (node (ref "U16") (pin "C2") (pinfunction "PI7_C2") (pintype "passive"))
    )
    (net (code "158") (name "/PI8") (class "Default")
      (node (ref "U16") (pin "D2") (pinfunction "PI8_D2") (pintype "passive"))
    )
    (net (code "159") (name "/PI9") (class "Default")
      (node (ref "U16") (pin "D3") (pinfunction "PI9_D3") (pintype "passive"))
    )
    (net (code "160") (name "/PI10") (class "Default")
      (node (ref "U16") (pin "E3") (pinfunction "PI10_E3") (pintype "passive"))
    )
    (net (code "161") (name "/PI11") (class "Default")
      (node (ref "U16") (pin "E4") (pinfunction "PI11_E4") (pintype "passive"))
    )
    (net (code "163") (name "/RESET#") (class "Default")
      (node (ref "B1") (pin "2") (pinfunction "B0_2") (pintype "passive"))
      (node (ref "B1") (pin "3") (pinfunction "B1_3") (pintype "passive"))
      (node (ref "C123") (pin "2") (pinfunction "2_2") (pintype "passive"))
      (node (ref "D2") (pin "1") (pinfunction "A_1") (pintype "passive"))
      (node (ref "R137") (pin "1") (pinfunction "1_1") (pintype "passive"))
      (node (ref "U16") (pin "J1") (pinfunction "NRST_J1") (pintype "passive"))
    )
    (net (code "164") (name "/SmartCard_IO") (class "Default")
      (node (ref "JP21") (pin "2") (pinfunction "NO_2") (pintype "passive"))
    )
    (net (code "165") (name "/TRACE_D0") (class "Default") (node (ref "JP2") (pin "1") (pintype "passive")))
    (net (code "166") (name "/TRACE_D1") (class "Default") (node (ref "JP1") (pin "1") (pintype "passive")))
    (net (code "167") (name "/ULPI_D0") (class "Default")
      (node (ref "U16") (pin "R2") (pinfunction "PA3_R2") (pintype "passive"))
    )
    (net (code "168") (name "/ULPI_D1") (class "Default")
      (node (ref "U16") (pin "R5") (pinfunction "PB0_R5") (pintype "passive"))
    )
    (net (code "169") (name "/ULPI_D2") (class "Default")
      (node (ref "U16") (pin "R4") (pinfunction "PB1_R4") (pintype "passive"))
    )
    (net (code "170") (name "/ULPI_D3") (class "Default")
      (node (ref "U16") (pin "R12") (pinfunction "PB10_R12") (pintype "passive"))
    )
    (net (code "171") (name "/ULPI_D4") (class "Default")
      (node (ref "U16") (pin "R13") (pinfunction "PB11_R13") (pintype "passive"))
    )
    (net (code "172") (name "/ULPI_D5") (class "Default")
      (node (ref "U16") (pin "P12") (pinfunction "PB12_P12") (pintype "passive"))
    )
    (net (code "173") (name "/ULPI_D6") (class "Default")
      (node (ref "U16") (pin "P13") (pinfunction "PB13_P13") (pintype "passive"))
    )
    (net (code "174") (name "/ULPI_D7") (class "Default")
      (node (ref "TP2") (pin "1") (pinfunction "1_1") (pintype "passive"))
      (node (ref "U16") (pin "A6") (pinfunction "PB5_A6") (pintype "passive"))
    )
    (net (code "176") (name "GND") (class "Default")
      (node (ref "B1") (pin "1") (pinfunction "A0_1") (pintype "passive"))
      (node (ref "B1") (pin "4") (pinfunction "A1_4") (pintype "passive"))
      (node (ref "BT1") (pin "2") (pinfunction "-_2") (pintype "passive"))
      (node (ref "C123") (pin "1") (pinfunction "1_1") (pintype "passive"))
      (node (ref "C33") (pin "2") (pinfunction "2_2") (pintype "passive"))
      (node (ref "C34") (pin "2") (pinfunction "2_2") (pintype "passive"))
      (node (ref "C35") (pin "2") (pinfunction "2_2") (pintype "passive"))
      (node (ref "C36") (pin "2") (pinfunction "2_2") (pintype "passive"))
      (node (ref "C37") (pin "2") (pinfunction "2_2") (pintype "passive"))
      (node (ref "C48") (pin "2") (pinfunction "2_2") (pintype "passive"))
      (node (ref "C49") (pin "2") (pinfunction "2_2") (pintype "passive"))
      (node (ref "C50") (pin "2") (pinfunction "2_2") (pintype "passive"))
      (node (ref "C53") (pin "2") (pinfunction "2_2") (pintype "passive"))
      (node (ref "C54") (pin "2") (pinfunction "2_2") (pintype "passive"))
      (node (ref "C56") (pin "2") (pinfunction "2_2") (pintype "passive"))
      (node (ref "C57") (pin "2") (pinfunction "2_2") (pintype "passive"))
      (node (ref "C58") (pin "2") (pinfunction "2_2") (pintype "passive"))
      (node (ref "C60") (pin "2") (pinfunction "2_2") (pintype "passive"))
      (node (ref "C61") (pin "2") (pinfunction "2_2") (pintype "passive"))
      (node (ref "C65") (pin "2") (pinfunction "2_2") (pintype "passive"))
      (node (ref "C66") (pin "2") (pinfunction "2_2") (pintype "passive"))
      (node (ref "C67") (pin "2") (pinfunction "2_2") (pintype "passive"))
      (node (ref "C68") (pin "2") (pinfunction "2_2") (pintype "passive"))
      (node (ref "C69") (pin "2") (pinfunction "2_2") (pintype "passive"))
      (node (ref "C70") (pin "2") (pinfunction "2_2") (pintype "passive"))
      (node (ref "C71") (pin "2") (pinfunction "2_2") (pintype "passive"))
      (node (ref "C72") (pin "2") (pinfunction "2_2") (pintype "passive"))
      (node (ref "C73") (pin "2") (pinfunction "2_2") (pintype "passive"))
      (node (ref "C74") (pin "2") (pinfunction "2_2") (pintype "passive"))
      (node (ref "C75") (pin "2") (pinfunction "2_2") (pintype "passive"))
      (node (ref "R71") (pin "2") (pinfunction "2_2") (pintype "passive"))
      (node (ref "R81") (pin "2") (pinfunction "2_2") (pintype "passive"))
      (node (ref "SW1") (pin "3") (pintype "passive"))
      (node (ref "SW2") (pin "3") (pintype "passive"))
      (node (ref "U16") (pin "D5") (pinfunction "VSS_SA_D5") (pintype "passive"))
      (node (ref "U16") (pin "D7") (pinfunction "VSS_D7") (pintype "passive"))
      (node (ref "U16") (pin "D8") (pinfunction "VSS_D8") (pintype "passive"))
      (node (ref "U16") (pin "D9") (pinfunction "VSS_D9") (pintype "passive"))
      (node (ref "U16") (pin "F12") (pinfunction "VSS_F12") (pintype "passive"))
      (node (ref "U16") (pin "F2") (pinfunction "VSS_F2") (pintype "passive"))
      (node (ref "U16") (pin "G12") (pinfunction "VSS_G12") (pintype "passive"))
      (node (ref "U16") (pin "G2") (pinfunction "VSS_G2") (pintype "passive"))
      (node (ref "U16") (pin "H12") (pinfunction "VSS_H12") (pintype "passive"))
      (node (ref "U16") (pin "M1") (pinfunction "VSSA_M1") (pintype "passive"))
      (node (ref "U16") (pin "M8") (pinfunction "VSS_M8") (pintype "passive"))
      (node (ref "U16") (pin "M9") (pinfunction "VSS_M9") (pintype "passive"))
      (node (ref "U16") (pin "N1") (pinfunction "VREF-_N1") (pintype "passive"))
    )
    (net (code "177") (name "Net-(BT1-+)") (class "Default")
      (node (ref "BT1") (pin "1") (pinfunction "+_1") (pintype "passive"))
      (node (ref "JP19") (pin "3") (pintype "passive"))
    )
    (net (code "178") (name "Net-(C33-Pad1)") (class "Default")
      (node (ref "C33") (pin "1") (pinfunction "1_1") (pintype "passive"))
      (node (ref "U16") (pin "F13") (pinfunction "VCAP_F13") (pintype "passive"))
    )
    (net (code "179") (name "Net-(C50-Pad1)") (class "Default")
      (node (ref "C50") (pin "1") (pinfunction "1_1") (pintype "passive"))
      (node (ref "U16") (pin "M10") (pinfunction "VCAP_M10") (pintype "passive"))
    )
    (net (code "180") (name "Net-(C70-Pad1)") (class "Default")
      (node (ref "C70") (pin "1") (pinfunction "1_1") (pintype "passive"))
      (node (ref "R84") (pin "1") (pinfunction "1_1") (pintype "passive"))
      (node (ref "X3") (pin "1") (pinfunction "1_1") (pintype "passive"))
    )
    (net (code "181") (name "Net-(C71-Pad1)") (class "Default")
      (node (ref "C71") (pin "1") (pinfunction "1_1") (pintype "passive"))
      (node (ref "R85") (pin "1") (pinfunction "1_1") (pintype "passive"))
      (node (ref "X3") (pin "4") (pinfunction "4_4") (pintype "passive"))
    )
    (net (code "182") (name "Net-(C73-Pad1)") (class "Default")
      (node (ref "C73") (pin "1") (pinfunction "1_1") (pintype "passive"))
      (node (ref "R86") (pin "2") (pinfunction "2_2") (pintype "passive"))
      (node (ref "X4") (pin "1") (pinfunction "1_1") (pintype "passive"))
    )
    (net (code "183") (name "Net-(D1-K)") (class "Default")
      (node (ref "D1") (pin "2") (pinfunction "K_2") (pintype "passive"))
      (node (ref "JP29") (pin "2") (pinfunction "NO_2") (pintype "passive"))
    )
    (net (code "184") (name "Net-(D2-K)") (class "Default")
      (node (ref "D2") (pin "2") (pinfunction "K_2") (pintype "passive"))
      (node (ref "JP34") (pin "1") (pinfunction "COMMON_1") (pintype "passive"))
    )
    (net (code "185") (name "Net-(JP4-NO)") (class "Default")
      (node (ref "JP4") (pin "2") (pinfunction "NO_2") (pintype "passive"))
      (node (ref "R81") (pin "1") (pinfunction "1_1") (pintype "passive"))
      (node (ref "U16") (pin "C6") (pinfunction "RFU_C6") (pintype "passive"))
    )
    (net (code "186") (name "Net-(R88-Pad2)") (class "Default")
      (node (ref "R88") (pin "2") (pinfunction "2_2") (pintype "passive"))
      (node (ref "SW1") (pin "2") (pintype "passive"))
    )
    (net (code "187") (name "Net-(R89-Pad2)") (class "Default")
      (node (ref "R89") (pin "2") (pinfunction "2_2") (pintype "passive"))
      (node (ref "SW2") (pin "2") (pintype "passive"))
    )
    (net (code "188") (name "Net-(U16A-PE3)") (class "Default")
      (node (ref "JP2") (pin "2") (pintype "passive"))
      (node (ref "U16") (pin "A1") (pinfunction "PE3_A1") (pintype "passive"))
    )
    (net (code "189") (name "Net-(U16A-PE4)") (class "Default")
      (node (ref "JP1") (pin "2") (pintype "passive"))
      (node (ref "U16") (pin "B1") (pinfunction "PE4_B1") (pintype "passive"))
    )
    (net (code "190") (name "Net-(U16B-BYPASS_REG)") (class "Default")
      (node (ref "R71") (pin "1") (pinfunction "1_1") (pintype "passive"))
      (node (ref "U16") (pin "L4") (pinfunction "BYPASS_REG_L4") (pintype "passive"))
    )
    (net (code "191") (name "Net-(U16B-VBAT)") (class "Default")
      (node (ref "JP19") (pin "2") (pintype "passive"))
      (node (ref "U16") (pin "C1") (pinfunction "VBAT_C1") (pintype "passive"))
    )
    (net (code "192") (name "VBUS_FS") (class "Default")
      (node (ref "U16") (pin "E15") (pinfunction "PA9_E15") (pintype "passive"))
    )
    (net (code "193") (name "VDDA") (class "Default")
      (node (ref "C69") (pin "1") (pinfunction "1_1") (pintype "passive"))
      (node (ref "C74") (pin "1") (pinfunction "1_1") (pintype "passive"))
      (node (ref "L3") (pin "1") (pinfunction "1_1") (pintype "passive"))
      (node (ref "R87") (pin "2") (pinfunction "2_2") (pintype "passive"))
      (node (ref "U16") (pin "R1") (pinfunction "VDDA_R1") (pintype "passive"))
    )
    (net (code "194") (name "VDD_MCU") (class "Default")
      (node (ref "C34") (pin "1") (pinfunction "1_1") (pintype "passive"))
      (node (ref "C35") (pin "1") (pinfunction "1_1") (pintype "passive"))
      (node (ref "C36") (pin "1") (pinfunction "1_1") (pintype "passive"))
      (node (ref "C37") (pin "1") (pinfunction "1_1") (pintype "passive"))
      (node (ref "C48") (pin "1") (pinfunction "1_1") (pintype "passive"))
      (node (ref "C49") (pin "1") (pinfunction "1_1") (pintype "passive"))
      (node (ref "C53") (pin "1") (pinfunction "1_1") (pintype "passive"))
      (node (ref "C54") (pin "1") (pinfunction "1_1") (pintype "passive"))
      (node (ref "C56") (pin "1") (pinfunction "1_1") (pintype "passive"))
      (node (ref "C57") (pin "1") (pinfunction "1_1") (pintype "passive"))
      (node (ref "C58") (pin "1") (pinfunction "1_1") (pintype "passive"))
      (node (ref "C60") (pin "1") (pinfunction "1_1") (pintype "passive"))
      (node (ref "C61") (pin "1") (pinfunction "1_1") (pintype "passive"))
      (node (ref "C65") (pin "1") (pinfunction "1_1") (pintype "passive"))
      (node (ref "C66") (pin "1") (pinfunction "1_1") (pintype "passive"))
      (node (ref "C67") (pin "1") (pinfunction "1_1") (pintype "passive"))
      (node (ref "L3") (pin "2") (pinfunction "2_2") (pintype "passive"))
      (node (ref "U16") (pin "C5") (pinfunction "VDD_SA_C5") (pintype "passive"))
      (node (ref "U16") (pin "C7") (pinfunction "VDD_C7") (pintype "passive"))
      (node (ref "U16") (pin "C8") (pinfunction "VDD_C8") (pintype "passive"))
      (node (ref "U16") (pin "C9") (pinfunction "VDD_C9") (pintype "passive"))
      (node (ref "U16") (pin "F3") (pinfunction "VDD_F3") (pintype "passive"))
      (node (ref "U16") (pin "G13") (pinfunction "VDD_G13") (pintype "passive"))
      (node (ref "U16") (pin "G3") (pinfunction "VDD_G3") (pintype "passive"))
      (node (ref "U16") (pin "H13") (pinfunction "VDD_H13") (pintype "passive"))
      (node (ref "U16") (pin "J12") (pinfunction "VDD_J12") (pintype "passive"))
      (node (ref "U16") (pin "J13") (pinfunction "VDD_J13") (pintype "passive"))
      (node (ref "U16") (pin "K4") (pinfunction "VDD_K4") (pintype "passive"))
      (node (ref "U16") (pin "N10") (pinfunction "VDD_N10") (pintype "passive"))
      (node (ref "U16") (pin "N8") (pinfunction "VDD_N8") (pintype "passive"))
      (node (ref "U16") (pin "N9") (pinfunction "VDD_N9") (pintype "passive"))
    )
    (net (code "195") (name "VREF+") (class "Default")
      (node (ref "C68") (pin "1") (pinfunction "1_1") (pintype "passive"))
      (node (ref "C75") (pin "1") (pinfunction "1_1") (pintype "passive"))
      (node (ref "R87") (pin "1") (pinfunction "1_1") (pintype "passive"))
      (node (ref "TP5") (pin "1") (pinfunction "1_1") (pintype "passive"))
      (node (ref "U16") (pin "P1") (pinfunction "VREF+_P1") (pintype "passive"))
    )
    (net (code "196") (name "unconnected-(X3-Pad2)") (class "Default")
      (node (ref "X3") (pin "2") (pinfunction "2_2") (pintype "passive"))
    )
    (net (code "197") (name "unconnected-(X3-Pad3)") (class "Default")
      (node (ref "X3") (pin "3") (pinfunction "3_3") (pintype "passive"))
    )
  )
)
